# GD32F103C8T6.net
KiCad netlist of a schematic drawn in EasyEDA Pro
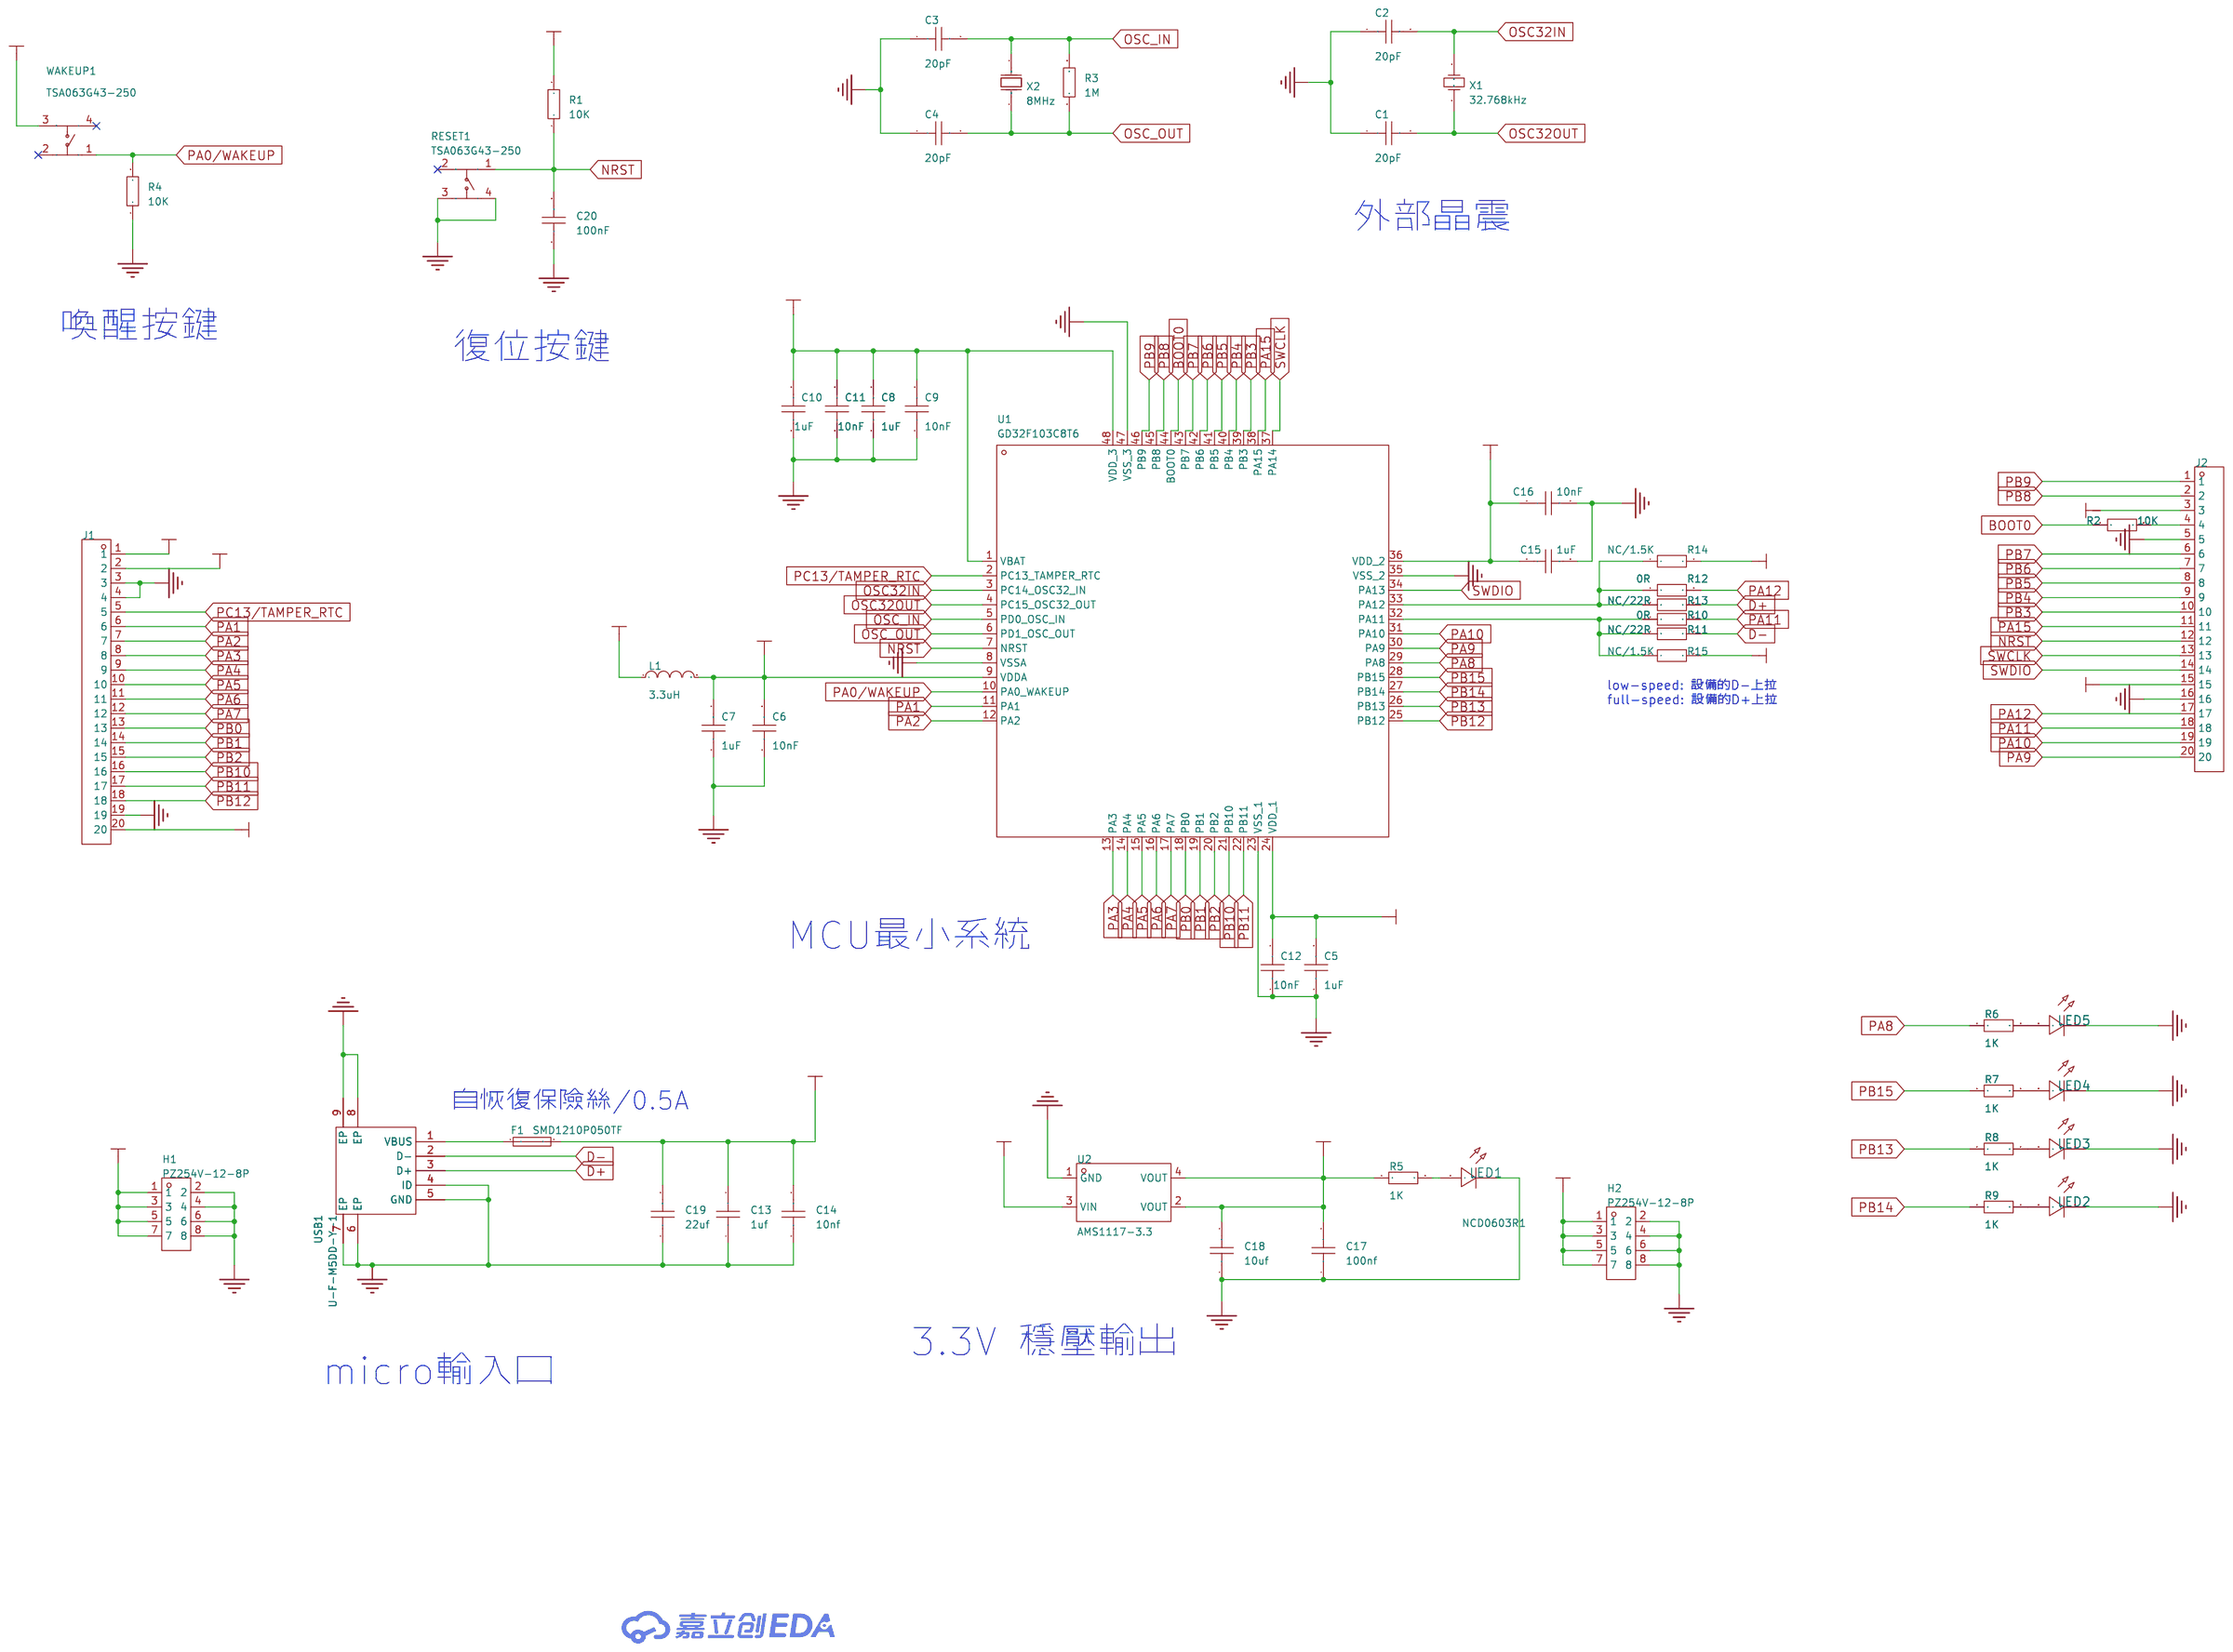
[diagram p0: schematic sheet]

(export (version "E")
  (design (tool "Eeschema 10.0.6"))
  (components
    (comp (ref "C1")
      (value "20pF")
      (footprint "easyedapro:C0603")
      (libsource (lib "easyedapro") (part "CapAcitance"))
    )
    (comp (ref "C2")
      (value "20pF")
      (footprint "easyedapro:C0603")
      (libsource (lib "easyedapro") (part "CapAcitance"))
    )
    (comp (ref "C3")
      (value "20pF")
      (footprint "easyedapro:C0603")
      (libsource (lib "easyedapro") (part "CapAcitance"))
    )
    (comp (ref "C4")
      (value "20pF")
      (footprint "easyedapro:C0603")
      (libsource (lib "easyedapro") (part "CapAcitance"))
    )
    (comp (ref "C5")
      (value "1uF")
      (footprint "easyedapro:C0603")
      (libsource (lib "easyedapro") (part "CapAcitance"))
    )
    (comp (ref "C6")
      (value "10nF")
      (footprint "easyedapro:C0603")
      (libsource (lib "easyedapro") (part "CapAcitance"))
    )
    (comp (ref "C7")
      (value "1uF")
      (footprint "easyedapro:C0603")
      (libsource (lib "easyedapro") (part "CapAcitance"))
    )
    (comp (ref "C8")
      (value "1uF")
      (footprint "easyedapro:C0603")
      (libsource (lib "easyedapro") (part "CapAcitance"))
    )
    (comp (ref "C9")
      (value "10nF")
      (footprint "easyedapro:C0603")
      (libsource (lib "easyedapro") (part "CapAcitance"))
    )
    (comp (ref "C10")
      (value "1uF")
      (footprint "easyedapro:C0603")
      (libsource (lib "easyedapro") (part "CapAcitance"))
    )
    (comp (ref "C11")
      (value "10nF")
      (footprint "easyedapro:C0603")
      (libsource (lib "easyedapro") (part "CapAcitance"))
    )
    (comp (ref "C12")
      (value "10nF")
      (footprint "easyedapro:C0603")
      (libsource (lib "easyedapro") (part "CapAcitance"))
    )
    (comp (ref "C13")
      (value "1uf")
      (footprint "easyedapro:C0603")
      (libsource (lib "easyedapro") (part "CapAcitance"))
    )
    (comp (ref "C14")
      (value "10nf")
      (footprint "easyedapro:C0603")
      (libsource (lib "easyedapro") (part "CapAcitance"))
    )
    (comp (ref "C15")
      (value "1uF")
      (footprint "easyedapro:C0603")
      (libsource (lib "easyedapro") (part "CapAcitance"))
    )
    (comp (ref "C16")
      (value "10nF")
      (footprint "easyedapro:C0603")
      (libsource (lib "easyedapro") (part "CapAcitance"))
    )
    (comp (ref "C17")
      (value "100nf")
      (footprint "easyedapro:C0603")
      (libsource (lib "easyedapro") (part "CapAcitance"))
    )
    (comp (ref "C18")
      (value "10uf")
      (footprint "easyedapro:C0603")
      (libsource (lib "easyedapro") (part "CapAcitance"))
    )
    (comp (ref "C19")
      (value "22uf")
      (footprint "easyedapro:C0603")
      (libsource (lib "easyedapro") (part "CapAcitance"))
    )
    (comp (ref "C20")
      (value "100nF")
      (footprint "easyedapro:C0603")
      (libsource (lib "easyedapro") (part "CapAcitance"))
    )
    (comp (ref "F1")
      (value "SMD1210P050TF")
      (footprint "easyedapro:F1210")
      (description "最大电压:13.2V;最大电流:100A;保持电流:500mA;跳闸电流:1A;")
      (fields (field (name "Manufacturer") "RUILON(瑞隆源)"))
      (libsource (lib "easyedapro") (part "SMD1210P050TF"))
    )
    (comp (ref "H1")
      (value "PZ254V-12-8P")
      (footprint "easyedapro:HDR-TH_8P-P2.54-V-M-R2-C4-S2.54")
      (fields (field (name "Manufacturer") "XFCN(兴飞)"))
      (libsource (lib "easyedapro") (part "PZ254V-12-8P"))
    )
    (comp (ref "H2")
      (value "PZ254V-12-8P")
      (footprint "easyedapro:HDR-TH_8P-P2.54-V-M-R2-C4-S2.54")
      (fields (field (name "Manufacturer") "XFCN(兴飞)"))
      (libsource (lib "easyedapro") (part "PZ254V-12-8P"))
    )
    (comp (ref "J1")
      (value "~")
      (footprint "easyedapro:HDR-TH_20P-P2.54-V-M-1")
      (libsource (lib "easyedapro") (part "HDR_2.54-1x20P"))
    )
    (comp (ref "J2")
      (value "~")
      (footprint "easyedapro:HDR-TH_20P-P2.54-V-M-1")
      (libsource (lib "easyedapro") (part "HDR_2.54-1x20P"))
    )
    (comp (ref "L1")
      (value "3.3uH")
      (footprint "easyedapro:L0603")
      (libsource (lib "easyedapro") (part "SDFL1608S100KTF"))
    )
    (comp (ref "LED1")
      (value "NCD0603R1")
      (footprint "easyedapro:LED_0603")
      (fields (field (name "Manufacturer") "国星光电"))
      (libsource (lib "easyedapro") (part "LED_R"))
    )
    (comp (ref "LED2")
      (value "NCD0603R1")
      (footprint "easyedapro:LED_0603")
      (fields (field (name "Manufacturer") "国星光电"))
      (libsource (lib "easyedapro") (part "LED_R"))
    )
    (comp (ref "LED3")
      (value "NCD0603R1")
      (footprint "easyedapro:LED_0603")
      (fields (field (name "Manufacturer") "国星光电"))
      (libsource (lib "easyedapro") (part "LED_R"))
    )
    (comp (ref "LED4")
      (value "NCD0603R1")
      (footprint "easyedapro:LED_0603")
      (fields (field (name "Manufacturer") "国星光电"))
      (libsource (lib "easyedapro") (part "LED_R"))
    )
    (comp (ref "LED5")
      (value "NCD0603R1")
      (footprint "easyedapro:LED_0603")
      (fields (field (name "Manufacturer") "国星光电"))
      (libsource (lib "easyedapro") (part "LED_R"))
    )
    (comp (ref "R1") (value "10K") (footprint "easyedapro:R0603") (libsource (lib "easyedapro") (part "电阻")))
    (comp (ref "R2") (value "10K") (footprint "easyedapro:R0603") (libsource (lib "easyedapro") (part "电阻")))
    (comp (ref "R3") (value "1M") (footprint "easyedapro:R0603") (libsource (lib "easyedapro") (part "电阻")))
    (comp (ref "R4") (value "10K") (footprint "easyedapro:R0603") (libsource (lib "easyedapro") (part "电阻")))
    (comp (ref "R5") (value "1K") (footprint "easyedapro:R0603") (libsource (lib "easyedapro") (part "电阻")))
    (comp (ref "R6") (value "1K") (footprint "easyedapro:R0603") (libsource (lib "easyedapro") (part "电阻")))
    (comp (ref "R7") (value "1K") (footprint "easyedapro:R0603") (libsource (lib "easyedapro") (part "电阻")))
    (comp (ref "R8") (value "1K") (footprint "easyedapro:R0603") (libsource (lib "easyedapro") (part "电阻")))
    (comp (ref "R9") (value "1K") (footprint "easyedapro:R0603") (libsource (lib "easyedapro") (part "电阻")))
    (comp (ref "R10") (value "0R") (footprint "easyedapro:R0603") (libsource (lib "easyedapro") (part "电阻")))
    (comp (ref "R11")
      (value "NC/22R")
      (footprint "easyedapro:R0603")
      (libsource (lib "easyedapro") (part "电阻"))
    )
    (comp (ref "R12") (value "0R") (footprint "easyedapro:R0603") (libsource (lib "easyedapro") (part "电阻")))
    (comp (ref "R13")
      (value "NC/22R")
      (footprint "easyedapro:R0603")
      (libsource (lib "easyedapro") (part "电阻"))
    )
    (comp (ref "R14")
      (value "NC/1.5K")
      (footprint "easyedapro:R0603")
      (libsource (lib "easyedapro") (part "电阻"))
    )
    (comp (ref "R15")
      (value "NC/1.5K")
      (footprint "easyedapro:R0603")
      (libsource (lib "easyedapro") (part "电阻"))
    )
    (comp (ref "RESET1")
      (value "TSA063G43-250")
      (footprint "easyedapro:KEY-SMD_4P-L6.0-W6.0-P4.50-LS10.0")
      (fields (field (name "Manufacturer") "BRIGHT(博瑞泰)"))
      (libsource (lib "easyedapro") (part "TSA063G43-250"))
    )
    (comp (ref "U1")
      (value "GD32F103C8T6")
      (footprint "easyedapro:TQFP-48_L7.0-W7.0-P0.50-LS9.0-BL")
      (description "CPU内核:CM3;程序存储容量:64KB;RAM总容量:20KB;GPIO端口数量:37;工作电压范围:2.6V~3.6V;CPU最大主频:108MHz;程序存储器类型:FLASH;")
      (fields (field (name "Manufacturer") "GigaDevice(兆易创新)"))
      (libsource (lib "easyedapro") (part "GD32F103C8T6"))
    )
    (comp (ref "U2")
      (value "AMS1117-3.3")
      (footprint "easyedapro:SOT-223-3_L6.5-W3.4-P2.30-LS7.0-BR")
      (description "输出类型:固定;最大输入电压:-;输出电压:3.3V;最大输出电流:1A;电源纹波抑制比(PSRR):72dB@(120Hz);输出极性:正极;")
      (fields (field (name "Manufacturer") "AMS"))
      (libsource (lib "easyedapro") (part "AMS1117-3.3"))
    )
    (comp (ref "USB1")
      (value "U-F-M5DD-Y-1")
      (footprint "easyedapro:MICRO-USB-SMD_U-F-M5DD-Y-1")
      (description "连接器类型:Micro-B;标准:USB 2.0;公母:母;端口数量:1;触点数量:5P;额定电流 - 电源:1A;")
      (fields (field (name "Manufacturer") "韩国韩荣"))
      (libsource (lib "easyedapro") (part "U-F-M5DD-Y-1"))
    )
    (comp (ref "WAKEUP1")
      (value "TSA063G43-250")
      (footprint "easyedapro:KEY-SMD_4P-L6.0-W6.0-P4.50-LS10.0")
      (fields (field (name "Manufacturer") "BRIGHT(博瑞泰)"))
      (libsource (lib "easyedapro") (part "TSA063G43-250"))
    )
    (comp (ref "X1")
      (value "32.768kHz")
      (footprint "easyedapro:OSC-TH_BD3.1-P0.8-D0.3")
      (description "晶振类型:直插晶振;频率:32.768kHz;常温频差:±10ppm;外接负载电容:12.5pF;频率稳定度(全温):-;")
      (fields (field (name "Manufacturer Part") "X308032768KGB2SC") (field (name "Manufacturer") "YXC(扬兴晶振)"))
      (libsource (lib "easyedapro") (part "X308032768KGB2SC"))
    )
    (comp (ref "X2")
      (value "8MHz")
      (footprint "easyedapro:OSC-TH_L10.0-W4.5-P5.00")
      (description "晶振类型:直插晶振;频率:8MHz;常温频差:±20ppm;外接负载电容:20pF;频率稳定度(全温):±30ppm;")
      (fields (field (name "Manufacturer Part") "X49SD8MSD2SC") (field (name "Manufacturer") "YXC(扬兴晶振)"))
      (libsource (lib "easyedapro") (part "X49SD8MSD2SC"))
    )
  )
  (nets
    (net (code "1") (name "BOOT0") (class "Default")
      (node (ref "R2") (pin "1") (pinfunction "1_1") (pintype "input"))
      (node (ref "U1") (pin "44") (pinfunction "BOOT0_44") (pintype "unspecified"))
    )
    (net (code "2") (name "D+") (class "Default")
      (node (ref "R13") (pin "2") (pinfunction "2_2") (pintype "input"))
      (node (ref "USB1") (pin "3") (pinfunction "D+_3") (pintype "unspecified"))
    )
    (net (code "3") (name "D-") (class "Default")
      (node (ref "R11") (pin "2") (pinfunction "2_2") (pintype "input"))
      (node (ref "USB1") (pin "2") (pinfunction "D-_2") (pintype "unspecified"))
    )
    (net (code "4") (name "GND") (class "Default")
      (node (ref "C1") (pin "1") (pinfunction "1_1") (pintype "input"))
      (node (ref "C10") (pin "1") (pinfunction "1_1") (pintype "input"))
      (node (ref "C11") (pin "1") (pinfunction "1_1") (pintype "input"))
      (node (ref "C12") (pin "1") (pinfunction "1_1") (pintype "input"))
      (node (ref "C13") (pin "1") (pinfunction "1_1") (pintype "input"))
      (node (ref "C14") (pin "1") (pinfunction "1_1") (pintype "input"))
      (node (ref "C15") (pin "2") (pinfunction "2_2") (pintype "input"))
      (node (ref "C16") (pin "2") (pinfunction "2_2") (pintype "input"))
      (node (ref "C17") (pin "1") (pinfunction "1_1") (pintype "input"))
      (node (ref "C18") (pin "1") (pinfunction "1_1") (pintype "input"))
      (node (ref "C19") (pin "1") (pinfunction "1_1") (pintype "input"))
      (node (ref "C2") (pin "1") (pinfunction "1_1") (pintype "input"))
      (node (ref "C20") (pin "1") (pinfunction "1_1") (pintype "input"))
      (node (ref "C3") (pin "1") (pinfunction "1_1") (pintype "input"))
      (node (ref "C4") (pin "1") (pinfunction "1_1") (pintype "input"))
      (node (ref "C5") (pin "1") (pinfunction "1_1") (pintype "input"))
      (node (ref "C6") (pin "1") (pinfunction "1_1") (pintype "input"))
      (node (ref "C7") (pin "1") (pinfunction "1_1") (pintype "input"))
      (node (ref "C8") (pin "1") (pinfunction "1_1") (pintype "input"))
      (node (ref "C9") (pin "1") (pinfunction "1_1") (pintype "input"))
      (node (ref "H1") (pin "2") (pinfunction "2_2") (pintype "unspecified"))
      (node (ref "H1") (pin "4") (pinfunction "4_4") (pintype "unspecified"))
      (node (ref "H1") (pin "6") (pinfunction "6_6") (pintype "unspecified"))
      (node (ref "H1") (pin "8") (pinfunction "8_8") (pintype "unspecified"))
      (node (ref "H2") (pin "2") (pinfunction "2_2") (pintype "unspecified"))
      (node (ref "H2") (pin "4") (pinfunction "4_4") (pintype "unspecified"))
      (node (ref "H2") (pin "6") (pinfunction "6_6") (pintype "unspecified"))
      (node (ref "H2") (pin "8") (pinfunction "8_8") (pintype "unspecified"))
      (node (ref "J1") (pin "19") (pinfunction "19_19") (pintype "input"))
      (node (ref "J1") (pin "3") (pinfunction "3_3") (pintype "input"))
      (node (ref "J1") (pin "4") (pinfunction "4_4") (pintype "input"))
      (node (ref "J2") (pin "16") (pinfunction "16_16") (pintype "input"))
      (node (ref "J2") (pin "5") (pinfunction "5_5") (pintype "input"))
      (node (ref "LED1") (pin "1") (pinfunction "C_1") (pintype "input"))
      (node (ref "LED2") (pin "1") (pinfunction "C_1") (pintype "input"))
      (node (ref "LED3") (pin "1") (pinfunction "C_1") (pintype "input"))
      (node (ref "LED4") (pin "1") (pinfunction "C_1") (pintype "input"))
      (node (ref "LED5") (pin "1") (pinfunction "C_1") (pintype "input"))
      (node (ref "R4") (pin "1") (pinfunction "1_1") (pintype "input"))
      (node (ref "RESET1") (pin "3") (pinfunction "3_3") (pintype "unspecified"))
      (node (ref "RESET1") (pin "4") (pinfunction "4_4") (pintype "unspecified"))
      (node (ref "U1") (pin "23") (pinfunction "VSS_1_23") (pintype "unspecified"))
      (node (ref "U1") (pin "35") (pinfunction "VSS_2_35") (pintype "unspecified"))
      (node (ref "U1") (pin "47") (pinfunction "VSS_3_47") (pintype "unspecified"))
      (node (ref "U1") (pin "8") (pinfunction "VSSA_8") (pintype "unspecified"))
      (node (ref "U2") (pin "1") (pinfunction "GND_1") (pintype "unspecified"))
      (node (ref "USB1") (pin "4") (pinfunction "ID_4") (pintype "unspecified"))
      (node (ref "USB1") (pin "5") (pinfunction "GND_5") (pintype "unspecified"))
      (node (ref "USB1") (pin "6") (pinfunction "EP_6") (pintype "unspecified"))
      (node (ref "USB1") (pin "7") (pinfunction "EP_7") (pintype "unspecified"))
      (node (ref "USB1") (pin "8") (pinfunction "EP_8") (pintype "unspecified"))
      (node (ref "USB1") (pin "9") (pinfunction "EP_9") (pintype "unspecified"))
    )
    (net (code "5") (name "NRST") (class "Default")
      (node (ref "C20") (pin "2") (pinfunction "2_2") (pintype "input"))
      (node (ref "J2") (pin "12") (pinfunction "12_12") (pintype "input"))
      (node (ref "R1") (pin "1") (pinfunction "1_1") (pintype "input"))
      (node (ref "RESET1") (pin "1") (pinfunction "1_1") (pintype "unspecified"))
      (node (ref "U1") (pin "7") (pinfunction "NRST_7") (pintype "unspecified"))
    )
    (net (code "6") (name "Net-(J2-Pad4)") (class "Default")
      (node (ref "J2") (pin "4") (pinfunction "4_4") (pintype "input"))
      (node (ref "R2") (pin "2") (pinfunction "2_2") (pintype "input"))
    )
    (net (code "7") (name "Net-(LED1-A)") (class "Default")
      (node (ref "LED1") (pin "2") (pinfunction "A_2") (pintype "input"))
      (node (ref "R5") (pin "2") (pinfunction "2_2") (pintype "input"))
    )
    (net (code "8") (name "Net-(LED2-A)") (class "Default")
      (node (ref "LED2") (pin "2") (pinfunction "A_2") (pintype "input"))
      (node (ref "R9") (pin "2") (pinfunction "2_2") (pintype "input"))
    )
    (net (code "9") (name "Net-(LED3-A)") (class "Default")
      (node (ref "LED3") (pin "2") (pinfunction "A_2") (pintype "input"))
      (node (ref "R8") (pin "2") (pinfunction "2_2") (pintype "input"))
    )
    (net (code "10") (name "Net-(LED4-A)") (class "Default")
      (node (ref "LED4") (pin "2") (pinfunction "A_2") (pintype "input"))
      (node (ref "R7") (pin "2") (pinfunction "2_2") (pintype "input"))
    )
    (net (code "11") (name "Net-(LED5-A)") (class "Default")
      (node (ref "LED5") (pin "2") (pinfunction "A_2") (pintype "input"))
      (node (ref "R6") (pin "2") (pinfunction "2_2") (pintype "input"))
    )
    (net (code "12") (name "Net-(U1-PA11)") (class "Default")
      (node (ref "R10") (pin "1") (pinfunction "1_1") (pintype "input"))
      (node (ref "R11") (pin "1") (pinfunction "1_1") (pintype "input"))
      (node (ref "R15") (pin "1") (pinfunction "1_1") (pintype "input"))
      (node (ref "U1") (pin "32") (pinfunction "PA11_32") (pintype "unspecified"))
    )
    (net (code "13") (name "Net-(U1-PA12)") (class "Default")
      (node (ref "R12") (pin "1") (pinfunction "1_1") (pintype "input"))
      (node (ref "R13") (pin "1") (pinfunction "1_1") (pintype "input"))
      (node (ref "R14") (pin "1") (pinfunction "1_1") (pintype "input"))
      (node (ref "U1") (pin "33") (pinfunction "PA12_33") (pintype "unspecified"))
    )
    (net (code "14") (name "Net-(USB1-VBUS)") (class "Default")
      (node (ref "F1") (pin "1") (pinfunction "1_1") (pintype "unspecified"))
      (node (ref "USB1") (pin "1") (pinfunction "VBUS_1") (pintype "unspecified"))
    )
    (net (code "15") (name "OSC32IN") (class "Default")
      (node (ref "C2") (pin "2") (pinfunction "2_2") (pintype "input"))
      (node (ref "U1") (pin "3") (pinfunction "PC14_OSC32_IN_3") (pintype "unspecified"))
      (node (ref "X1") (pin "1") (pinfunction "OSC1_1") (pintype "unspecified"))
    )
    (net (code "16") (name "OSC32OUT") (class "Default")
      (node (ref "C1") (pin "2") (pinfunction "2_2") (pintype "input"))
      (node (ref "U1") (pin "4") (pinfunction "PC15_OSC32_OUT_4") (pintype "unspecified"))
      (node (ref "X1") (pin "2") (pinfunction "OSC2_2") (pintype "unspecified"))
    )
    (net (code "17") (name "OSC_IN") (class "Default")
      (node (ref "C3") (pin "2") (pinfunction "2_2") (pintype "input"))
      (node (ref "R3") (pin "2") (pinfunction "2_2") (pintype "input"))
      (node (ref "U1") (pin "5") (pinfunction "PD0_OSC_IN_5") (pintype "unspecified"))
      (node (ref "X2") (pin "2") (pinfunction "OSC2_2") (pintype "input"))
    )
    (net (code "18") (name "OSC_OUT") (class "Default")
      (node (ref "C4") (pin "2") (pinfunction "2_2") (pintype "input"))
      (node (ref "R3") (pin "1") (pinfunction "1_1") (pintype "input"))
      (node (ref "U1") (pin "6") (pinfunction "PD1_OSC_OUT_6") (pintype "unspecified"))
      (node (ref "X2") (pin "1") (pinfunction "OSC1_1") (pintype "input"))
    )
    (net (code "19") (name "PA0{slash}WAKEUP") (class "Default")
      (node (ref "R4") (pin "2") (pinfunction "2_2") (pintype "input"))
      (node (ref "U1") (pin "10") (pinfunction "PA0_WAKEUP_10") (pintype "unspecified"))
      (node (ref "WAKEUP1") (pin "1") (pinfunction "1_1") (pintype "unspecified"))
    )
    (net (code "20") (name "PA1") (class "Default")
      (node (ref "J1") (pin "6") (pinfunction "6_6") (pintype "input"))
      (node (ref "U1") (pin "11") (pinfunction "PA1_11") (pintype "unspecified"))
    )
    (net (code "21") (name "PA2") (class "Default")
      (node (ref "J1") (pin "7") (pinfunction "7_7") (pintype "input"))
      (node (ref "U1") (pin "12") (pinfunction "PA2_12") (pintype "unspecified"))
    )
    (net (code "22") (name "PA3") (class "Default")
      (node (ref "J1") (pin "8") (pinfunction "8_8") (pintype "input"))
      (node (ref "U1") (pin "13") (pinfunction "PA3_13") (pintype "unspecified"))
    )
    (net (code "23") (name "PA4") (class "Default")
      (node (ref "J1") (pin "9") (pinfunction "9_9") (pintype "input"))
      (node (ref "U1") (pin "14") (pinfunction "PA4_14") (pintype "unspecified"))
    )
    (net (code "24") (name "PA5") (class "Default")
      (node (ref "J1") (pin "10") (pinfunction "10_10") (pintype "input"))
      (node (ref "U1") (pin "15") (pinfunction "PA5_15") (pintype "unspecified"))
    )
    (net (code "25") (name "PA6") (class "Default")
      (node (ref "J1") (pin "11") (pinfunction "11_11") (pintype "input"))
      (node (ref "U1") (pin "16") (pinfunction "PA6_16") (pintype "unspecified"))
    )
    (net (code "26") (name "PA7") (class "Default")
      (node (ref "J1") (pin "12") (pinfunction "12_12") (pintype "input"))
      (node (ref "U1") (pin "17") (pinfunction "PA7_17") (pintype "unspecified"))
    )
    (net (code "27") (name "PA8") (class "Default")
      (node (ref "R6") (pin "1") (pinfunction "1_1") (pintype "input"))
      (node (ref "U1") (pin "29") (pinfunction "PA8_29") (pintype "unspecified"))
    )
    (net (code "28") (name "PA9") (class "Default")
      (node (ref "J2") (pin "20") (pinfunction "20_20") (pintype "input"))
      (node (ref "U1") (pin "30") (pinfunction "PA9_30") (pintype "unspecified"))
    )
    (net (code "29") (name "PA10") (class "Default")
      (node (ref "J2") (pin "19") (pinfunction "19_19") (pintype "input"))
      (node (ref "U1") (pin "31") (pinfunction "PA10_31") (pintype "unspecified"))
    )
    (net (code "30") (name "PA11") (class "Default")
      (node (ref "J2") (pin "18") (pinfunction "18_18") (pintype "input"))
      (node (ref "R10") (pin "2") (pinfunction "2_2") (pintype "input"))
    )
    (net (code "31") (name "PA12") (class "Default")
      (node (ref "J2") (pin "17") (pinfunction "17_17") (pintype "input"))
      (node (ref "R12") (pin "2") (pinfunction "2_2") (pintype "input"))
    )
    (net (code "32") (name "PA15") (class "Default")
      (node (ref "J2") (pin "11") (pinfunction "11_11") (pintype "input"))
      (node (ref "U1") (pin "38") (pinfunction "PA15_38") (pintype "unspecified"))
    )
    (net (code "33") (name "PB0") (class "Default")
      (node (ref "J1") (pin "13") (pinfunction "13_13") (pintype "input"))
      (node (ref "U1") (pin "18") (pinfunction "PB0_18") (pintype "unspecified"))
    )
    (net (code "34") (name "PB1") (class "Default")
      (node (ref "J1") (pin "14") (pinfunction "14_14") (pintype "input"))
      (node (ref "U1") (pin "19") (pinfunction "PB1_19") (pintype "unspecified"))
    )
    (net (code "35") (name "PB2") (class "Default")
      (node (ref "J1") (pin "15") (pinfunction "15_15") (pintype "input"))
      (node (ref "U1") (pin "20") (pinfunction "PB2_20") (pintype "unspecified"))
    )
    (net (code "36") (name "PB3") (class "Default")
      (node (ref "J2") (pin "10") (pinfunction "10_10") (pintype "input"))
      (node (ref "U1") (pin "39") (pinfunction "PB3_39") (pintype "unspecified"))
    )
    (net (code "37") (name "PB4") (class "Default")
      (node (ref "J2") (pin "9") (pinfunction "9_9") (pintype "input"))
      (node (ref "U1") (pin "40") (pinfunction "PB4_40") (pintype "unspecified"))
    )
    (net (code "38") (name "PB5") (class "Default")
      (node (ref "J2") (pin "8") (pinfunction "8_8") (pintype "input"))
      (node (ref "U1") (pin "41") (pinfunction "PB5_41") (pintype "unspecified"))
    )
    (net (code "39") (name "PB6") (class "Default")
      (node (ref "J2") (pin "7") (pinfunction "7_7") (pintype "input"))
      (node (ref "U1") (pin "42") (pinfunction "PB6_42") (pintype "unspecified"))
    )
    (net (code "40") (name "PB7") (class "Default")
      (node (ref "J2") (pin "6") (pinfunction "6_6") (pintype "input"))
      (node (ref "U1") (pin "43") (pinfunction "PB7_43") (pintype "unspecified"))
    )
    (net (code "41") (name "PB8") (class "Default")
      (node (ref "J2") (pin "2") (pinfunction "2_2") (pintype "input"))
      (node (ref "U1") (pin "45") (pinfunction "PB8_45") (pintype "unspecified"))
    )
    (net (code "42") (name "PB9") (class "Default")
      (node (ref "J2") (pin "1") (pinfunction "1_1") (pintype "input"))
      (node (ref "U1") (pin "46") (pinfunction "PB9_46") (pintype "unspecified"))
    )
    (net (code "43") (name "PB10") (class "Default")
      (node (ref "J1") (pin "16") (pinfunction "16_16") (pintype "input"))
      (node (ref "U1") (pin "21") (pinfunction "PB10_21") (pintype "unspecified"))
    )
    (net (code "44") (name "PB11") (class "Default")
      (node (ref "J1") (pin "17") (pinfunction "17_17") (pintype "input"))
      (node (ref "U1") (pin "22") (pinfunction "PB11_22") (pintype "unspecified"))
    )
    (net (code "45") (name "PB12") (class "Default")
      (node (ref "J1") (pin "18") (pinfunction "18_18") (pintype "input"))
      (node (ref "U1") (pin "25") (pinfunction "PB12_25") (pintype "unspecified"))
    )
    (net (code "46") (name "PB13") (class "Default")
      (node (ref "R8") (pin "1") (pinfunction "1_1") (pintype "input"))
      (node (ref "U1") (pin "26") (pinfunction "PB13_26") (pintype "unspecified"))
    )
    (net (code "47") (name "PB14") (class "Default")
      (node (ref "R9") (pin "1") (pinfunction "1_1") (pintype "input"))
      (node (ref "U1") (pin "27") (pinfunction "PB14_27") (pintype "unspecified"))
    )
    (net (code "48") (name "PB15") (class "Default")
      (node (ref "R7") (pin "1") (pinfunction "1_1") (pintype "input"))
      (node (ref "U1") (pin "28") (pinfunction "PB15_28") (pintype "unspecified"))
    )
    (net (code "49") (name "PC13{slash}TAMPER_RTC") (class "Default")
      (node (ref "J1") (pin "5") (pinfunction "5_5") (pintype "input"))
      (node (ref "U1") (pin "2") (pinfunction "PC13_TAMPER_RTC_2") (pintype "unspecified"))
    )
    (net (code "50") (name "SWCLK") (class "Default")
      (node (ref "J2") (pin "13") (pinfunction "13_13") (pintype "input"))
      (node (ref "U1") (pin "37") (pinfunction "PA14_37") (pintype "unspecified"))
    )
    (net (code "51") (name "SWDIO") (class "Default")
      (node (ref "J2") (pin "14") (pinfunction "14_14") (pintype "input"))
      (node (ref "U1") (pin "34") (pinfunction "PA13_34") (pintype "unspecified"))
    )
    (net (code "52") (name "VCC_3V3") (class "Default")
      (node (ref "C10") (pin "2") (pinfunction "2_2") (pintype "input"))
      (node (ref "C11") (pin "2") (pinfunction "2_2") (pintype "input"))
      (node (ref "C12") (pin "2") (pinfunction "2_2") (pintype "input"))
      (node (ref "C15") (pin "1") (pinfunction "1_1") (pintype "input"))
      (node (ref "C16") (pin "1") (pinfunction "1_1") (pintype "input"))
      (node (ref "C17") (pin "2") (pinfunction "2_2") (pintype "input"))
      (node (ref "C18") (pin "2") (pinfunction "2_2") (pintype "input"))
      (node (ref "C5") (pin "2") (pinfunction "2_2") (pintype "input"))
      (node (ref "C8") (pin "2") (pinfunction "2_2") (pintype "input"))
      (node (ref "C9") (pin "2") (pinfunction "2_2") (pintype "input"))
      (node (ref "H2") (pin "1") (pinfunction "1_1") (pintype "unspecified"))
      (node (ref "H2") (pin "3") (pinfunction "3_3") (pintype "unspecified"))
      (node (ref "H2") (pin "5") (pinfunction "5_5") (pintype "unspecified"))
      (node (ref "H2") (pin "7") (pinfunction "7_7") (pintype "unspecified"))
      (node (ref "J1") (pin "1") (pinfunction "1_1") (pintype "input"))
      (node (ref "J1") (pin "20") (pinfunction "20_20") (pintype "input"))
      (node (ref "J2") (pin "15") (pinfunction "15_15") (pintype "input"))
      (node (ref "J2") (pin "3") (pinfunction "3_3") (pintype "input"))
      (node (ref "L1") (pin "1") (pinfunction "1_1") (pintype "unspecified"))
      (node (ref "R1") (pin "2") (pinfunction "2_2") (pintype "input"))
      (node (ref "R14") (pin "2") (pinfunction "2_2") (pintype "input"))
      (node (ref "R15") (pin "2") (pinfunction "2_2") (pintype "input"))
      (node (ref "R5") (pin "1") (pinfunction "1_1") (pintype "input"))
      (node (ref "U1") (pin "1") (pinfunction "VBAT_1") (pintype "unspecified"))
      (node (ref "U1") (pin "24") (pinfunction "VDD_1_24") (pintype "unspecified"))
      (node (ref "U1") (pin "36") (pinfunction "VDD_2_36") (pintype "unspecified"))
      (node (ref "U1") (pin "48") (pinfunction "VDD_3_48") (pintype "unspecified"))
      (node (ref "U2") (pin "2") (pinfunction "VOUT_2") (pintype "unspecified"))
      (node (ref "U2") (pin "4") (pinfunction "VOUT_4") (pintype "unspecified"))
      (node (ref "WAKEUP1") (pin "3") (pinfunction "3_3") (pintype "unspecified"))
    )
    (net (code "53") (name "VDDA") (class "Default")
      (node (ref "C6") (pin "2") (pinfunction "2_2") (pintype "input"))
      (node (ref "C7") (pin "2") (pinfunction "2_2") (pintype "input"))
      (node (ref "J1") (pin "2") (pinfunction "2_2") (pintype "input"))
      (node (ref "L1") (pin "2") (pinfunction "2_2") (pintype "unspecified"))
      (node (ref "U1") (pin "9") (pinfunction "VDDA_9") (pintype "unspecified"))
    )
    (net (code "54") (name "VIN_5V") (class "Default")
      (node (ref "C13") (pin "2") (pinfunction "2_2") (pintype "input"))
      (node (ref "C14") (pin "2") (pinfunction "2_2") (pintype "input"))
      (node (ref "C19") (pin "2") (pinfunction "2_2") (pintype "input"))
      (node (ref "F1") (pin "2") (pinfunction "2_2") (pintype "unspecified"))
      (node (ref "H1") (pin "1") (pinfunction "1_1") (pintype "unspecified"))
      (node (ref "H1") (pin "3") (pinfunction "3_3") (pintype "unspecified"))
      (node (ref "H1") (pin "5") (pinfunction "5_5") (pintype "unspecified"))
      (node (ref "H1") (pin "7") (pinfunction "7_7") (pintype "unspecified"))
      (node (ref "U2") (pin "3") (pinfunction "VIN_3") (pintype "unspecified"))
    )
    (net (code "55") (name "unconnected-(RESET1-Pad2)") (class "Default")
      (node (ref "RESET1") (pin "2") (pinfunction "2_2") (pintype "unspecified+no_connect"))
    )
    (net (code "56") (name "unconnected-(WAKEUP1-Pad2)") (class "Default")
      (node (ref "WAKEUP1") (pin "2") (pinfunction "2_2") (pintype "unspecified+no_connect"))
    )
    (net (code "57") (name "unconnected-(WAKEUP1-Pad4)") (class "Default")
      (node (ref "WAKEUP1") (pin "4") (pinfunction "4_4") (pintype "unspecified+no_connect"))
    )
  )
)
